# POWER_PMIC.net
KiCad netlist of a schematic drawn in Altium Designer
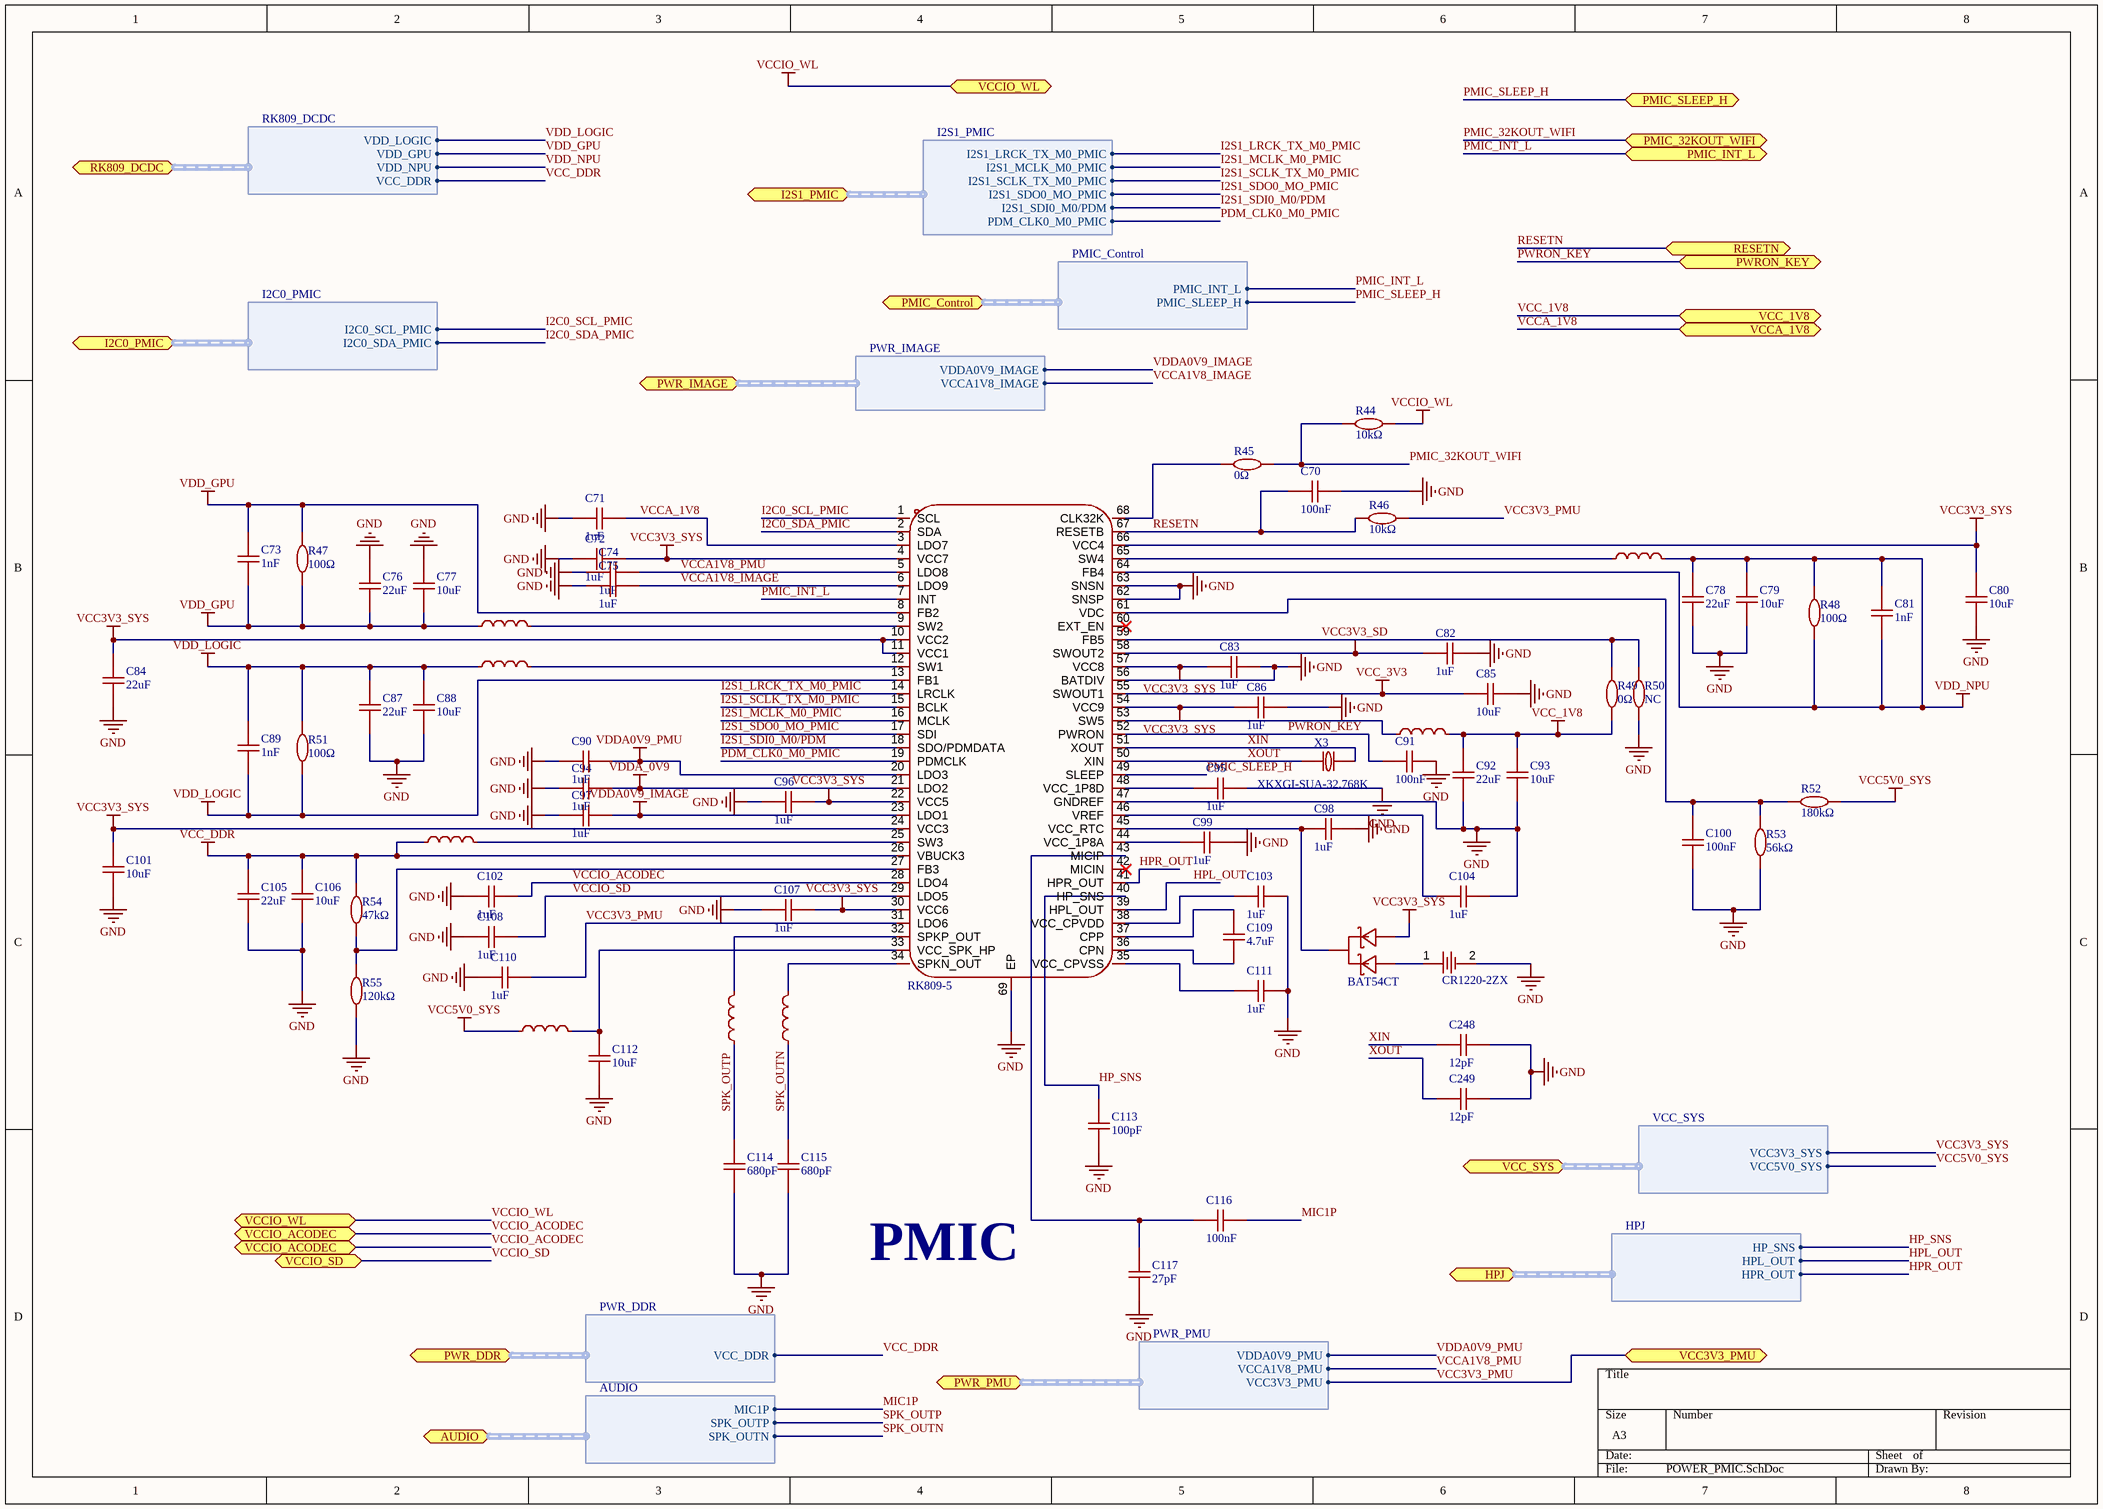
[diagram p0: POWER_PMIC.SchDoc]

(export (version "E")
  (design (tool "Eeschema 10.0.6"))
  (components
    (comp (ref "BT1")
      (value "CR1220-2ZX")
      (footprint "BAT-SMD_CR1220-2ZX")
      (description "Battery")
      (libsource (lib "Connector") (part "CR1220-2ZX"))
    )
    (comp (ref "C70")
      (value "100nF")
      (footprint "C0402")
      (description "50V 100nF X7R ±10% 0402 Ceramic Capacitors ROHS")
      (libsource (lib "RLC") (part "100nF"))
    )
    (comp (ref "C71")
      (value "1uF")
      (footprint "C0402")
      (description "50V 1uF X5R ±10% 0402 Ceramic Capacitors ROHS")
      (libsource (lib "RLC") (part "1uF"))
    )
    (comp (ref "C72")
      (value "1uF")
      (footprint "C0402")
      (description "50V 1uF X5R ±10% 0402 Ceramic Capacitors ROHS")
      (libsource (lib "RLC") (part "1uF"))
    )
    (comp (ref "C73")
      (value "1nF")
      (footprint "C0402")
      (description "50V 1nF X7R ±10% 0402 Ceramic Capacitors ROHS")
      (libsource (lib "RLC") (part "1nF"))
    )
    (comp (ref "C74")
      (value "1uF")
      (footprint "C0402")
      (description "50V 1uF X5R ±10% 0402 Ceramic Capacitors ROHS")
      (libsource (lib "RLC") (part "1uF"))
    )
    (comp (ref "C75")
      (value "1uF")
      (footprint "C0402")
      (description "50V 1uF X5R ±10% 0402 Ceramic Capacitors ROHS")
      (libsource (lib "RLC") (part "1uF"))
    )
    (comp (ref "C76")
      (value "22uF")
      (footprint "C0603")
      (description "16V 22uF X5R ±20% 0603 Ceramic Capacitors ROHS")
      (libsource (lib "RLC") (part "22uF"))
    )
    (comp (ref "C77")
      (value "10uF")
      (footprint "C0603")
      (description "10V 10uF X5R ±10% 0603 Ceramic Capacitors ROHS")
      (libsource (lib "RLC") (part "10uF"))
    )
    (comp (ref "C78")
      (value "22uF")
      (footprint "C0603")
      (description "16V 22uF X5R ±20% 0603 Ceramic Capacitors ROHS")
      (libsource (lib "RLC") (part "22uF"))
    )
    (comp (ref "C79")
      (value "10uF")
      (footprint "C0603")
      (description "10V 10uF X5R ±10% 0603 Ceramic Capacitors ROHS")
      (libsource (lib "RLC") (part "10uF"))
    )
    (comp (ref "C80")
      (value "10uF")
      (footprint "C0603")
      (description "10V 10uF X5R ±10% 0603 Ceramic Capacitors ROHS")
      (libsource (lib "RLC") (part "10uF"))
    )
    (comp (ref "C81")
      (value "1nF")
      (footprint "C0402")
      (description "50V 1nF X7R ±10% 0402 Ceramic Capacitors ROHS")
      (libsource (lib "RLC") (part "1nF"))
    )
    (comp (ref "C82")
      (value "1uF")
      (footprint "C0402")
      (description "50V 1uF X5R ±10% 0402 Ceramic Capacitors ROHS")
      (libsource (lib "RLC") (part "1uF"))
    )
    (comp (ref "C83")
      (value "1uF")
      (footprint "C0402")
      (description "50V 1uF X5R ±10% 0402 Ceramic Capacitors ROHS")
      (libsource (lib "RLC") (part "1uF"))
    )
    (comp (ref "C84")
      (value "22uF")
      (footprint "C0603")
      (description "16V 22uF X5R ±20% 0603 Ceramic Capacitors ROHS")
      (libsource (lib "RLC") (part "22uF"))
    )
    (comp (ref "C85")
      (value "10uF")
      (footprint "C0603")
      (description "10V 10uF X5R ±10% 0603 Ceramic Capacitors ROHS")
      (libsource (lib "RLC") (part "10uF"))
    )
    (comp (ref "C86")
      (value "1uF")
      (footprint "C0402")
      (description "50V 1uF X5R ±10% 0402 Ceramic Capacitors ROHS")
      (libsource (lib "RLC") (part "1uF"))
    )
    (comp (ref "C87")
      (value "22uF")
      (footprint "C0603")
      (description "16V 22uF X5R ±20% 0603 Ceramic Capacitors ROHS")
      (libsource (lib "RLC") (part "22uF"))
    )
    (comp (ref "C88")
      (value "10uF")
      (footprint "C0603")
      (description "10V 10uF X5R ±10% 0603 Ceramic Capacitors ROHS")
      (libsource (lib "RLC") (part "10uF"))
    )
    (comp (ref "C89")
      (value "1nF")
      (footprint "C0402")
      (description "50V 1nF X7R ±10% 0402 Ceramic Capacitors ROHS")
      (libsource (lib "RLC") (part "1nF"))
    )
    (comp (ref "C90")
      (value "1uF")
      (footprint "C0402")
      (description "50V 1uF X5R ±10% 0402 Ceramic Capacitors ROHS")
      (libsource (lib "RLC") (part "1uF"))
    )
    (comp (ref "C91")
      (value "100nF")
      (footprint "C0402")
      (description "50V 100nF X7R ±10% 0402 Ceramic Capacitors ROHS")
      (libsource (lib "RLC") (part "100nF"))
    )
    (comp (ref "C92")
      (value "22uF")
      (footprint "C0603")
      (description "16V 22uF X5R ±20% 0603 Ceramic Capacitors ROHS")
      (libsource (lib "RLC") (part "22uF"))
    )
    (comp (ref "C93")
      (value "10uF")
      (footprint "C0603")
      (description "10V 10uF X5R ±10% 0603 Ceramic Capacitors ROHS")
      (libsource (lib "RLC") (part "10uF"))
    )
    (comp (ref "C94")
      (value "1uF")
      (footprint "C0402")
      (description "50V 1uF X5R ±10% 0402 Ceramic Capacitors ROHS")
      (libsource (lib "RLC") (part "1uF"))
    )
    (comp (ref "C95")
      (value "1uF")
      (footprint "C0402")
      (description "50V 1uF X5R ±10% 0402 Ceramic Capacitors ROHS")
      (libsource (lib "RLC") (part "1uF"))
    )
    (comp (ref "C96")
      (value "1uF")
      (footprint "C0402")
      (description "50V 1uF X5R ±10% 0402 Ceramic Capacitors ROHS")
      (libsource (lib "RLC") (part "1uF"))
    )
    (comp (ref "C97")
      (value "1uF")
      (footprint "C0402")
      (description "50V 1uF X5R ±10% 0402 Ceramic Capacitors ROHS")
      (libsource (lib "RLC") (part "1uF"))
    )
    (comp (ref "C98")
      (value "1uF")
      (footprint "C0402")
      (description "50V 1uF X5R ±10% 0402 Ceramic Capacitors ROHS")
      (libsource (lib "RLC") (part "1uF"))
    )
    (comp (ref "C99")
      (value "1uF")
      (footprint "C0402")
      (description "50V 1uF X5R ±10% 0402 Ceramic Capacitors ROHS")
      (libsource (lib "RLC") (part "1uF"))
    )
    (comp (ref "C100")
      (value "100nF")
      (footprint "C0402")
      (description "50V 100nF X7R ±10% 0402 Ceramic Capacitors ROHS")
      (libsource (lib "RLC") (part "100nF"))
    )
    (comp (ref "C101")
      (value "10uF")
      (footprint "C0603")
      (description "10V 10uF X5R ±10% 0603 Ceramic Capacitors ROHS")
      (libsource (lib "RLC") (part "10uF"))
    )
    (comp (ref "C102")
      (value "1uF")
      (footprint "C0402")
      (description "50V 1uF X5R ±10% 0402 Ceramic Capacitors ROHS")
      (libsource (lib "RLC") (part "1uF"))
    )
    (comp (ref "C103")
      (value "1uF")
      (footprint "C0402")
      (description "50V 1uF X5R ±10% 0402 Ceramic Capacitors ROHS")
      (libsource (lib "RLC") (part "1uF"))
    )
    (comp (ref "C104")
      (value "1uF")
      (footprint "C0402")
      (description "50V 1uF X5R ±10% 0402 Ceramic Capacitors ROHS")
      (libsource (lib "RLC") (part "1uF"))
    )
    (comp (ref "C105")
      (value "22uF")
      (footprint "C0603")
      (description "16V 22uF X5R ±20% 0603 Ceramic Capacitors ROHS")
      (libsource (lib "RLC") (part "22uF"))
    )
    (comp (ref "C106")
      (value "10uF")
      (footprint "C0603")
      (description "10V 10uF X5R ±10% 0603 Ceramic Capacitors ROHS")
      (libsource (lib "RLC") (part "10uF"))
    )
    (comp (ref "C107")
      (value "1uF")
      (footprint "C0402")
      (description "50V 1uF X5R ±10% 0402 Ceramic Capacitors ROHS")
      (libsource (lib "RLC") (part "1uF"))
    )
    (comp (ref "C108")
      (value "1uF")
      (footprint "C0402")
      (description "50V 1uF X5R ±10% 0402 Ceramic Capacitors ROHS")
      (libsource (lib "RLC") (part "1uF"))
    )
    (comp (ref "C109")
      (value "4.7uF")
      (footprint "C0402")
      (description "10V 4.7uF X5R ±20% 0402 Ceramic Capacitors ROHS")
      (libsource (lib "RLC") (part "4.7uF"))
    )
    (comp (ref "C110")
      (value "1uF")
      (footprint "C0402")
      (description "50V 1uF X5R ±10% 0402 Ceramic Capacitors ROHS")
      (libsource (lib "RLC") (part "1uF"))
    )
    (comp (ref "C111")
      (value "1uF")
      (footprint "C0402")
      (description "50V 1uF X5R ±10% 0402 Ceramic Capacitors ROHS")
      (libsource (lib "RLC") (part "1uF"))
    )
    (comp (ref "C112")
      (value "10uF")
      (footprint "C0603")
      (description "10V 10uF X5R ±10% 0603 Ceramic Capacitors ROHS")
      (libsource (lib "RLC") (part "10uF"))
    )
    (comp (ref "C113")
      (value "100pF")
      (footprint "C0402")
      (description "50V 100pF C0G ±5% 0402 Ceramic Capacitors ROHS")
      (libsource (lib "RLC") (part "100pF"))
    )
    (comp (ref "C114")
      (value "680pF")
      (footprint "C0402")
      (description "50V 680pF C0G ±5% 0402 Ceramic Capacitors ROHS")
      (libsource (lib "RLC") (part "680pF"))
    )
    (comp (ref "C115")
      (value "680pF")
      (footprint "C0402")
      (description "50V 680pF C0G ±5% 0402 Ceramic Capacitors ROHS")
      (libsource (lib "RLC") (part "680pF"))
    )
    (comp (ref "C116")
      (value "100nF")
      (footprint "C0402")
      (description "50V 100nF X7R ±10% 0402 Ceramic Capacitors ROHS")
      (libsource (lib "RLC") (part "100nF"))
    )
    (comp (ref "C117")
      (value "27pF")
      (footprint "C0402")
      (description "50V 27pF C0G ±5% 0402 Ceramic Capacitors ROHS")
      (libsource (lib "RLC") (part "27pF"))
    )
    (comp (ref "C248")
      (value "12pF")
      (footprint "C0402")
      (description "50V 12pF C0G ±5% 0402 Ceramic Capacitors ROHS")
      (libsource (lib "RLC") (part "12pF"))
    )
    (comp (ref "C249")
      (value "12pF")
      (footprint "C0402")
      (description "50V 12pF C0G ±5% 0402 Ceramic Capacitors ROHS")
      (libsource (lib "RLC") (part "12pF"))
    )
    (comp (ref "D9")
      (value "BAT54CT")
      (footprint "SOT-523-3_L1.6-W0.8-P1.00-LS1.6-BR")
      (description "电压:30V 电流:200mA 特性：低正向压降。 快速开关。 PN结保护环，用于瞬态和ESD保护")
      (libsource (lib "LED") (part "BAT54CT"))
    )
    (comp (ref "L3")
      (value "470nH")
      (footprint "IND-SMD_L2.0-W1.6_MHCHL201610A-1R0M-Q8A")
      (description "0806 MCS20FC-R47MHC")
      (fields
        (field (name "MANUFACTURER") "Sunltech(顺磁)")
        (field (name "MANUFACTURER PART") "SLW4030S1R0NST")
      )
      (libsource (lib "RLC") (part "MCS20FC-R47MHC"))
    )
    (comp (ref "L4")
      (value "470nH")
      (footprint "IND-SMD_L2.0-W1.6_MHCHL201610A-1R0M-Q8A")
      (description "0806 MCS20FC-R47MHC")
      (fields
        (field (name "MANUFACTURER") "Sunltech(顺磁)")
        (field (name "MANUFACTURER PART") "SLW4030S1R0NST")
      )
      (libsource (lib "RLC") (part "MCS20FC-R47MHC"))
    )
    (comp (ref "L5")
      (value "470nH")
      (footprint "IND-SMD_L2.0-W1.6_MHCHL201610A-1R0M-Q8A")
      (description "0806 MCS20FC-R47MHC")
      (fields
        (field (name "MANUFACTURER") "Sunltech(顺磁)")
        (field (name "MANUFACTURER PART") "SLW4030S1R0NST")
      )
      (libsource (lib "RLC") (part "MCS20FC-R47MHC"))
    )
    (comp (ref "L6")
      (value "470nH")
      (footprint "IND-SMD_L2.0-W1.6_MHCHL201610A-1R0M-Q8A")
      (description "0806 MCS20FC-R47MHC")
      (fields
        (field (name "MANUFACTURER") "Sunltech(顺磁)")
        (field (name "MANUFACTURER PART") "SLW4030S1R0NST")
      )
      (libsource (lib "RLC") (part "MCS20FC-R47MHC"))
    )
    (comp (ref "L7")
      (value "470nH")
      (footprint "IND-SMD_L2.0-W1.6_MHCHL201610A-1R0M-Q8A")
      (description "0806 MCS20FC-R47MHC")
      (fields
        (field (name "MANUFACTURER") "Sunltech(顺磁)")
        (field (name "MANUFACTURER PART") "SLW4030S1R0NST")
      )
      (libsource (lib "RLC") (part "MCS20FC-R47MHC"))
    )
    (comp (ref "L8")
      (value "180Ω")
      (footprint "L0603")
      (description "单路 0603磁珠 阻抗180Ω@100MHz")
      (fields (field (name "MANUFACTURER") "cjiang(长江微电)") (field (name "MANUFACTURER PART") "FNR6020S4R7MT"))
      (libsource (lib "RLC") (part "BLM18PG181SN1D"))
    )
    (comp (ref "L9")
      (value "180Ω")
      (footprint "L0603")
      (description "单路 0603磁珠 阻抗180Ω@100MHz")
      (fields (field (name "MANUFACTURER") "cjiang(长江微电)") (field (name "MANUFACTURER PART") "FNR6020S4R7MT"))
      (libsource (lib "RLC") (part "BLM18PG181SN1D"))
    )
    (comp (ref "L10")
      (value "180Ω")
      (footprint "L0603")
      (description "单路 0603磁珠 阻抗180Ω@100MHz")
      (fields (field (name "MANUFACTURER") "cjiang(长江微电)") (field (name "MANUFACTURER PART") "FNR6020S4R7MT"))
      (libsource (lib "RLC") (part "BLM18PG181SN1D"))
    )
    (comp (ref "R44")
      (value "10kΩ")
      (footprint "R0402")
      (description "62.5mW 10kΩ 50V ±100ppm/℃ Thick Film Resistor ±1% 0402 Chip Resistor - Surface Mount ROHS")
      (libsource (lib "RLC") (part "10kΩ"))
    )
    (comp (ref "R45")
      (value "0Ω")
      (footprint "R0402")
      (description "0Ω 62.5mW 50V Thick Film Resistor ±1% 0402 Chip Resistor - Surface Mount ROHS")
      (libsource (lib "RLC") (part "0Ω"))
    )
    (comp (ref "R46")
      (value "10kΩ")
      (footprint "R0402")
      (description "62.5mW 10kΩ 50V ±100ppm/℃ Thick Film Resistor ±1% 0402 Chip Resistor - Surface Mount ROHS")
      (libsource (lib "RLC") (part "10kΩ"))
    )
    (comp (ref "R47")
      (value "100Ω")
      (footprint "R0402")
      (description "100Ω 62.5mW 50V ±100ppm/℃ Thick Film Resistor ±1% 0402 Chip Resistor - Surface Mount ROHS")
      (libsource (lib "RLC") (part "100Ω"))
    )
    (comp (ref "R48")
      (value "100Ω")
      (footprint "R0402")
      (description "100Ω 62.5mW 50V ±100ppm/℃ Thick Film Resistor ±1% 0402 Chip Resistor - Surface Mount ROHS")
      (libsource (lib "RLC") (part "100Ω"))
    )
    (comp (ref "R49")
      (value "0Ω")
      (footprint "R0402")
      (description "0Ω 62.5mW 50V Thick Film Resistor ±1% 0402 Chip Resistor - Surface Mount ROHS")
      (libsource (lib "RLC") (part "0Ω"))
    )
    (comp (ref "R50")
      (value "NC")
      (footprint "R0402")
      (description "0Ω 62.5mW 50V Thick Film Resistor ±1% 0402 Chip Resistor - Surface Mount ROHS")
      (libsource (lib "RLC") (part "0Ω"))
    )
    (comp (ref "R51")
      (value "100Ω")
      (footprint "R0402")
      (description "100Ω 62.5mW 50V ±100ppm/℃ Thick Film Resistor ±1% 0402 Chip Resistor - Surface Mount ROHS")
      (libsource (lib "RLC") (part "100Ω"))
    )
    (comp (ref "R52")
      (value "180kΩ")
      (footprint "R0402")
      (description "62.5mW 180kΩ 50V ±100ppm/℃ Thick Film Resistor ±1% 0402 Chip Resistor - Surface Mount ROHS")
      (libsource (lib "RLC") (part "180kΩ"))
    )
    (comp (ref "R53")
      (value "56kΩ")
      (footprint "R0402")
      (description "56kΩ 62.5mW 50V ±100ppm/℃ Thick Film Resistor ±1% 0402 Chip Resistor - Surface Mount ROHS")
      (libsource (lib "RLC") (part "56kΩ"))
    )
    (comp (ref "R54")
      (value "47kΩ")
      (footprint "R0402")
      (description "62.5mW 47kΩ 50V ±100ppm/℃ Thick Film Resistor ±1% 0402 Chip Resistor - Surface Mount ROHS")
      (libsource (lib "RLC") (part "47kΩ"))
    )
    (comp (ref "R55")
      (value "120kΩ")
      (footprint "R0402")
      (description "62.5mW 120kΩ 50V ±100ppm/℃ Thick Film Resistor ±1% 0402 Chip Resistor - Surface Mount ROHS")
      (libsource (lib "RLC") (part "120kΩ"))
    )
    (comp (ref "U20")
      (value "RK809-5")
      (footprint "QFN-68_L7.0-W7.0-P0.35-BL-EP5.5")
      (libsource (lib "IC") (part "RK809-5"))
    )
    (comp (ref "X3")
      (value "XKXGI-SUA-32.768K")
      (footprint "CRYSTAL-SMD_L3.2-W1.5-1")
      (description "SMD3215-2P XKXGI-SUA-32.768K")
      (libsource (lib "OSC") (part "XKXGI-SUA-32.768K"))
    )
  )
  (nets
    (net (code "11") (name "/HPL_OUT") (class "Default")
      (node (ref "U20") (pin "39") (pinfunction "HPL_OUT_39") (pintype "passive"))
    )
    (net (code "12") (name "/HPR_OUT") (class "Default")
      (node (ref "U20") (pin "41") (pinfunction "HPR_OUT_41") (pintype "passive"))
    )
    (net (code "13") (name "/HP_SNS") (class "Default")
      (node (ref "C113") (pin "2") (pinfunction "2_2") (pintype "passive"))
      (node (ref "U20") (pin "40") (pinfunction "HP_SNS_40") (pintype "passive"))
    )
    (net (code "14") (name "/I2C0_SCL_PMIC") (class "Default")
      (node (ref "U20") (pin "1") (pinfunction "SCL_1") (pintype "passive"))
    )
    (net (code "15") (name "/I2C0_SDA_PMIC") (class "Default")
      (node (ref "U20") (pin "2") (pinfunction "SDA_2") (pintype "passive"))
    )
    (net (code "16") (name "/I2S1_LRCK_TX_M0_PMIC") (class "Default")
      (node (ref "U20") (pin "14") (pinfunction "LRCLK_14") (pintype "passive"))
    )
    (net (code "17") (name "/I2S1_MCLK_M0_PMIC") (class "Default")
      (node (ref "U20") (pin "16") (pinfunction "MCLK_16") (pintype "passive"))
    )
    (net (code "18") (name "/I2S1_SCLK_TX_M0_PMIC") (class "Default")
      (node (ref "U20") (pin "15") (pinfunction "BCLK_15") (pintype "passive"))
    )
    (net (code "19") (name "/I2S1_SDI0_M0{slash}PDM") (class "Default")
      (node (ref "U20") (pin "18") (pinfunction "SDO/PDMDATA_18") (pintype "passive"))
    )
    (net (code "20") (name "/I2S1_SDO0_MO_PMIC") (class "Default")
      (node (ref "U20") (pin "17") (pinfunction "SDI_17") (pintype "passive"))
    )
    (net (code "21") (name "/MIC1P") (class "Default")
      (node (ref "C116") (pin "2") (pinfunction "2_2") (pintype "passive"))
    )
    (net (code "22") (name "/PDM_CLK0_M0_PMIC") (class "Default")
      (node (ref "U20") (pin "19") (pinfunction "PDMCLK_19") (pintype "passive"))
    )
    (net (code "23") (name "/PMIC_32KOUT_WIFI") (class "Default")
      (node (ref "R44") (pin "1") (pinfunction "1_1") (pintype "passive"))
      (node (ref "R45") (pin "2") (pinfunction "2_2") (pintype "passive"))
    )
    (net (code "24") (name "/PMIC_INT_L") (class "Default")
      (node (ref "U20") (pin "7") (pinfunction "INT_7") (pintype "passive"))
    )
    (net (code "25") (name "/PMIC_SLEEP_H") (class "Default")
      (node (ref "U20") (pin "49") (pinfunction "SLEEP_49") (pintype "passive"))
    )
    (net (code "26") (name "/PWRON_KEY") (class "Default")
      (node (ref "C91") (pin "1") (pinfunction "1_1") (pintype "passive"))
      (node (ref "U20") (pin "52") (pinfunction "PWRON_52") (pintype "passive"))
    )
    (net (code "27") (name "/RESETN") (class "Default")
      (node (ref "C70") (pin "1") (pinfunction "1_1") (pintype "passive"))
      (node (ref "R46") (pin "1") (pinfunction "1_1") (pintype "passive"))
      (node (ref "U20") (pin "67") (pinfunction "RESETB_67") (pintype "passive"))
    )
    (net (code "28") (name "/SPK_OUTN") (class "Default")
      (node (ref "C115") (pin "2") (pinfunction "2_2") (pintype "passive"))
      (node (ref "L9") (pin "1") (pinfunction "1_1") (pintype "passive"))
    )
    (net (code "29") (name "/SPK_OUTP") (class "Default")
      (node (ref "C114") (pin "2") (pinfunction "2_2") (pintype "passive"))
      (node (ref "L8") (pin "1") (pinfunction "1_1") (pintype "passive"))
    )
    (net (code "30") (name "/VCC3V3_PMU") (class "Default")
      (node (ref "C110") (pin "1") (pinfunction "1_1") (pintype "passive"))
      (node (ref "R46") (pin "2") (pinfunction "2_2") (pintype "passive"))
      (node (ref "U20") (pin "31") (pinfunction "LDO6_31") (pintype "passive"))
    )
    (net (code "31") (name "/VCCA1V8_IMAGE") (class "Default")
      (node (ref "C75") (pin "1") (pinfunction "1_1") (pintype "passive"))
      (node (ref "U20") (pin "6") (pinfunction "LDO9_6") (pintype "passive"))
    )
    (net (code "32") (name "/VCCA1V8_PMU") (class "Default")
      (node (ref "C74") (pin "1") (pinfunction "1_1") (pintype "passive"))
      (node (ref "U20") (pin "5") (pinfunction "LDO8_5") (pintype "passive"))
    )
    (net (code "33") (name "/VCCA_1V8") (class "Default")
      (node (ref "C71") (pin "1") (pinfunction "1_1") (pintype "passive"))
      (node (ref "U20") (pin "3") (pinfunction "LDO7_3") (pintype "passive"))
    )
    (net (code "34") (name "/VCCIO_ACODEC") (class "Default")
      (node (ref "C102") (pin "1") (pinfunction "1_1") (pintype "passive"))
      (node (ref "U20") (pin "28") (pinfunction "LDO4_28") (pintype "passive"))
    )
    (net (code "35") (name "/VCCIO_SD") (class "Default")
      (node (ref "C108") (pin "1") (pinfunction "1_1") (pintype "passive"))
      (node (ref "U20") (pin "29") (pinfunction "LDO5_29") (pintype "passive"))
    )
    (net (code "36") (name "/XIN") (class "Default")
      (node (ref "C248") (pin "1") (pinfunction "1_1") (pintype "passive"))
      (node (ref "U20") (pin "51") (pinfunction "XOUT_51") (pintype "passive"))
      (node (ref "X3") (pin "2") (pinfunction "2_2") (pintype "passive"))
    )
    (net (code "37") (name "/XOUT") (class "Default")
      (node (ref "C249") (pin "1") (pinfunction "1_1") (pintype "passive"))
      (node (ref "U20") (pin "50") (pinfunction "XIN_50") (pintype "passive"))
      (node (ref "X3") (pin "1") (pinfunction "1_1") (pintype "passive"))
    )
    (net (code "48") (name "GND") (class "Default")
      (node (ref "BT1") (pin "2") (pinfunction "2_2") (pintype "passive"))
      (node (ref "C100") (pin "1") (pinfunction "1_1") (pintype "passive"))
      (node (ref "C101") (pin "1") (pinfunction "1_1") (pintype "passive"))
      (node (ref "C102") (pin "2") (pinfunction "2_2") (pintype "passive"))
      (node (ref "C103") (pin "1") (pinfunction "1_1") (pintype "passive"))
      (node (ref "C104") (pin "1") (pinfunction "1_1") (pintype "passive"))
      (node (ref "C105") (pin "1") (pinfunction "1_1") (pintype "passive"))
      (node (ref "C106") (pin "1") (pinfunction "1_1") (pintype "passive"))
      (node (ref "C107") (pin "2") (pinfunction "2_2") (pintype "passive"))
      (node (ref "C108") (pin "2") (pinfunction "2_2") (pintype "passive"))
      (node (ref "C110") (pin "2") (pinfunction "2_2") (pintype "passive"))
      (node (ref "C111") (pin "2") (pinfunction "2_2") (pintype "passive"))
      (node (ref "C112") (pin "1") (pinfunction "1_1") (pintype "passive"))
      (node (ref "C113") (pin "1") (pinfunction "1_1") (pintype "passive"))
      (node (ref "C114") (pin "1") (pinfunction "1_1") (pintype "passive"))
      (node (ref "C115") (pin "1") (pinfunction "1_1") (pintype "passive"))
      (node (ref "C117") (pin "1") (pinfunction "1_1") (pintype "passive"))
      (node (ref "C248") (pin "2") (pinfunction "2_2") (pintype "passive"))
      (node (ref "C249") (pin "2") (pinfunction "2_2") (pintype "passive"))
      (node (ref "C70") (pin "2") (pinfunction "2_2") (pintype "passive"))
      (node (ref "C71") (pin "2") (pinfunction "2_2") (pintype "passive"))
      (node (ref "C72") (pin "2") (pinfunction "2_2") (pintype "passive"))
      (node (ref "C74") (pin "2") (pinfunction "2_2") (pintype "passive"))
      (node (ref "C75") (pin "2") (pinfunction "2_2") (pintype "passive"))
      (node (ref "C76") (pin "2") (pinfunction "2_2") (pintype "passive"))
      (node (ref "C77") (pin "2") (pinfunction "2_2") (pintype "passive"))
      (node (ref "C78") (pin "1") (pinfunction "1_1") (pintype "passive"))
      (node (ref "C79") (pin "1") (pinfunction "1_1") (pintype "passive"))
      (node (ref "C80") (pin "1") (pinfunction "1_1") (pintype "passive"))
      (node (ref "C82") (pin "1") (pinfunction "1_1") (pintype "passive"))
      (node (ref "C83") (pin "2") (pinfunction "2_2") (pintype "passive"))
      (node (ref "C84") (pin "1") (pinfunction "1_1") (pintype "passive"))
      (node (ref "C85") (pin "1") (pinfunction "1_1") (pintype "passive"))
      (node (ref "C86") (pin "2") (pinfunction "2_2") (pintype "passive"))
      (node (ref "C87") (pin "1") (pinfunction "1_1") (pintype "passive"))
      (node (ref "C88") (pin "1") (pinfunction "1_1") (pintype "passive"))
      (node (ref "C90") (pin "2") (pinfunction "2_2") (pintype "passive"))
      (node (ref "C91") (pin "2") (pinfunction "2_2") (pintype "passive"))
      (node (ref "C92") (pin "1") (pinfunction "1_1") (pintype "passive"))
      (node (ref "C93") (pin "1") (pinfunction "1_1") (pintype "passive"))
      (node (ref "C94") (pin "2") (pinfunction "2_2") (pintype "passive"))
      (node (ref "C95") (pin "2") (pinfunction "2_2") (pintype "passive"))
      (node (ref "C96") (pin "2") (pinfunction "2_2") (pintype "passive"))
      (node (ref "C97") (pin "2") (pinfunction "2_2") (pintype "passive"))
      (node (ref "C98") (pin "1") (pinfunction "1_1") (pintype "passive"))
      (node (ref "C99") (pin "2") (pinfunction "2_2") (pintype "passive"))
      (node (ref "R50") (pin "2") (pinfunction "2_2") (pintype "passive"))
      (node (ref "R53") (pin "1") (pinfunction "1_1") (pintype "passive"))
      (node (ref "R55") (pin "1") (pinfunction "1_1") (pintype "passive"))
      (node (ref "U20") (pin "47") (pinfunction "GNDREF_47") (pintype "passive"))
      (node (ref "U20") (pin "56") (pinfunction "BATDIV_56") (pintype "passive"))
      (node (ref "U20") (pin "62") (pinfunction "SNSP_62") (pintype "passive"))
      (node (ref "U20") (pin "63") (pinfunction "SNSN_63") (pintype "passive"))
      (node (ref "U20") (pin "69") (pinfunction "EP_69") (pintype "passive"))
    )
    (net (code "49") (name "Net-(BT1-Pad1)") (class "Default")
      (node (ref "BT1") (pin "1") (pinfunction "1_1") (pintype "passive"))
      (node (ref "D9") (pin "1") (pinfunction "A_1") (pintype "passive"))
    )
    (net (code "50") (name "Net-(D9-K)") (class "Default")
      (node (ref "C98") (pin "2") (pinfunction "2_2") (pintype "passive"))
      (node (ref "D9") (pin "3") (pinfunction "K_3") (pintype "passive"))
      (node (ref "U20") (pin "45") (pinfunction "VCC_RTC_45") (pintype "passive"))
    )
    (net (code "51") (name "Net-(U20-CLK32K)") (class "Default")
      (node (ref "R45") (pin "1") (pinfunction "1_1") (pintype "passive"))
      (node (ref "U20") (pin "68") (pinfunction "CLK32K_68") (pintype "passive"))
    )
    (net (code "52") (name "Net-(U20-CPN)") (class "Default")
      (node (ref "C109") (pin "1") (pinfunction "1_1") (pintype "passive"))
      (node (ref "U20") (pin "36") (pinfunction "CPN_36") (pintype "passive"))
    )
    (net (code "53") (name "Net-(U20-CPP)") (class "Default")
      (node (ref "C109") (pin "2") (pinfunction "2_2") (pintype "passive"))
      (node (ref "U20") (pin "37") (pinfunction "CPP_37") (pintype "passive"))
    )
    (net (code "54") (name "Net-(U20-FB3)") (class "Default")
      (node (ref "R54") (pin "1") (pinfunction "1_1") (pintype "passive"))
      (node (ref "R55") (pin "2") (pinfunction "2_2") (pintype "passive"))
      (node (ref "U20") (pin "27") (pinfunction "FB3_27") (pintype "passive"))
    )
    (net (code "55") (name "Net-(U20-FB5)") (class "Default")
      (node (ref "R49") (pin "2") (pinfunction "2_2") (pintype "passive"))
      (node (ref "R50") (pin "1") (pinfunction "1_1") (pintype "passive"))
      (node (ref "U20") (pin "59") (pinfunction "FB5_59") (pintype "passive"))
    )
    (net (code "56") (name "Net-(U20-MICIP)") (class "Default")
      (node (ref "C116") (pin "1") (pinfunction "1_1") (pintype "passive"))
      (node (ref "C117") (pin "2") (pinfunction "2_2") (pintype "passive"))
      (node (ref "U20") (pin "43") (pinfunction "MICIP_43") (pintype "passive"))
    )
    (net (code "57") (name "Net-(U20-SPKN_OUT)") (class "Default")
      (node (ref "L9") (pin "2") (pinfunction "2_2") (pintype "passive"))
      (node (ref "U20") (pin "34") (pinfunction "SPKN_OUT_34") (pintype "passive"))
    )
    (net (code "58") (name "Net-(U20-SPKP_OUT)") (class "Default")
      (node (ref "L8") (pin "2") (pinfunction "2_2") (pintype "passive"))
      (node (ref "U20") (pin "32") (pinfunction "SPKP_OUT_32") (pintype "passive"))
    )
    (net (code "59") (name "Net-(U20-SW1)") (class "Default")
      (node (ref "L5") (pin "2") (pinfunction "2_2") (pintype "passive"))
      (node (ref "U20") (pin "12") (pinfunction "SW1_12") (pintype "passive"))
    )
    (net (code "60") (name "Net-(U20-SW2)") (class "Default")
      (node (ref "L4") (pin "2") (pinfunction "2_2") (pintype "passive"))
      (node (ref "U20") (pin "9") (pinfunction "SW2_9") (pintype "passive"))
    )
    (net (code "61") (name "Net-(U20-SW3)") (class "Default")
      (node (ref "L7") (pin "2") (pinfunction "2_2") (pintype "passive"))
      (node (ref "U20") (pin "25") (pinfunction "SW3_25") (pintype "passive"))
    )
    (net (code "62") (name "Net-(U20-SW4)") (class "Default")
      (node (ref "L3") (pin "1") (pinfunction "1_1") (pintype "passive"))
      (node (ref "U20") (pin "65") (pinfunction "SW4_65") (pintype "passive"))
    )
    (net (code "63") (name "Net-(U20-SW5)") (class "Default")
      (node (ref "L6") (pin "1") (pinfunction "1_1") (pintype "passive"))
      (node (ref "U20") (pin "53") (pinfunction "SW5_53") (pintype "passive"))
    )
    (net (code "64") (name "Net-(U20-VCC_1P8A)") (class "Default")
      (node (ref "C99") (pin "1") (pinfunction "1_1") (pintype "passive"))
      (node (ref "U20") (pin "44") (pinfunction "VCC_1P8A_44") (pintype "passive"))
    )
    (net (code "65") (name "Net-(U20-VCC_1P8D)") (class "Default")
      (node (ref "C95") (pin "1") (pinfunction "1_1") (pintype "passive"))
      (node (ref "U20") (pin "48") (pinfunction "VCC_1P8D_48") (pintype "passive"))
    )
    (net (code "66") (name "Net-(U20-VCC_CPVDD)") (class "Default")
      (node (ref "C103") (pin "2") (pinfunction "2_2") (pintype "passive"))
      (node (ref "U20") (pin "38") (pinfunction "VCC_CPVDD_38") (pintype "passive"))
    )
    (net (code "67") (name "Net-(U20-VCC_CPVSS)") (class "Default")
      (node (ref "C111") (pin "1") (pinfunction "1_1") (pintype "passive"))
      (node (ref "U20") (pin "35") (pinfunction "VCC_CPVSS_35") (pintype "passive"))
    )
    (net (code "68") (name "Net-(U20-VCC_SPK_HP)") (class "Default")
      (node (ref "C112") (pin "2") (pinfunction "2_2") (pintype "passive"))
      (node (ref "L10") (pin "2") (pinfunction "2_2") (pintype "passive"))
      (node (ref "U20") (pin "33") (pinfunction "VCC_SPK_HP_33") (pintype "passive"))
    )
    (net (code "69") (name "Net-(U20-VDC)") (class "Default")
      (node (ref "C100") (pin "2") (pinfunction "2_2") (pintype "passive"))
      (node (ref "R52") (pin "1") (pinfunction "1_1") (pintype "passive"))
      (node (ref "R53") (pin "2") (pinfunction "2_2") (pintype "passive"))
      (node (ref "U20") (pin "61") (pinfunction "VDC_61") (pintype "passive"))
    )
    (net (code "70") (name "Net-(U20-VREF)") (class "Default")
      (node (ref "C104") (pin "2") (pinfunction "2_2") (pintype "passive"))
      (node (ref "U20") (pin "46") (pinfunction "VREF_46") (pintype "passive"))
    )
    (net (code "71") (name "VCC3V3_SD") (class "Default")
      (node (ref "C82") (pin "2") (pinfunction "2_2") (pintype "passive"))
      (node (ref "U20") (pin "58") (pinfunction "SWOUT2_58") (pintype "passive"))
    )
    (net (code "72") (name "VCC3V3_SYS") (class "Default")
      (node (ref "C101") (pin "2") (pinfunction "2_2") (pintype "passive"))
      (node (ref "C107") (pin "1") (pinfunction "1_1") (pintype "passive"))
      (node (ref "C72") (pin "1") (pinfunction "1_1") (pintype "passive"))
      (node (ref "C80") (pin "2") (pinfunction "2_2") (pintype "passive"))
      (node (ref "C83") (pin "1") (pinfunction "1_1") (pintype "passive"))
      (node (ref "C84") (pin "2") (pinfunction "2_2") (pintype "passive"))
      (node (ref "C86") (pin "1") (pinfunction "1_1") (pintype "passive"))
      (node (ref "C96") (pin "1") (pinfunction "1_1") (pintype "passive"))
      (node (ref "D9") (pin "2") (pinfunction "A_2") (pintype "passive"))
      (node (ref "U20") (pin "10") (pinfunction "VCC2_10") (pintype "passive"))
      (node (ref "U20") (pin "11") (pinfunction "VCC1_11") (pintype "passive"))
      (node (ref "U20") (pin "22") (pinfunction "VCC5_22") (pintype "passive"))
      (node (ref "U20") (pin "24") (pinfunction "VCC3_24") (pintype "passive"))
      (node (ref "U20") (pin "30") (pinfunction "VCC6_30") (pintype "passive"))
      (node (ref "U20") (pin "4") (pinfunction "VCC7_4") (pintype "passive"))
      (node (ref "U20") (pin "54") (pinfunction "VCC9_54") (pintype "passive"))
      (node (ref "U20") (pin "57") (pinfunction "VCC8_57") (pintype "passive"))
      (node (ref "U20") (pin "66") (pinfunction "VCC4_66") (pintype "passive"))
    )
    (net (code "73") (name "VCC5V0_SYS") (class "Default")
      (node (ref "L10") (pin "1") (pinfunction "1_1") (pintype "passive"))
      (node (ref "R52") (pin "2") (pinfunction "2_2") (pintype "passive"))
    )
    (net (code "74") (name "VCCIO_WL") (class "Default")
      (node (ref "R44") (pin "2") (pinfunction "2_2") (pintype "passive"))
    )
    (net (code "75") (name "VCC_1V8") (class "Default")
      (node (ref "C92") (pin "2") (pinfunction "2_2") (pintype "passive"))
      (node (ref "C93") (pin "2") (pinfunction "2_2") (pintype "passive"))
      (node (ref "L6") (pin "2") (pinfunction "2_2") (pintype "passive"))
      (node (ref "R49") (pin "1") (pinfunction "1_1") (pintype "passive"))
    )
    (net (code "76") (name "VCC_3V3") (class "Default")
      (node (ref "C85") (pin "2") (pinfunction "2_2") (pintype "passive"))
      (node (ref "U20") (pin "55") (pinfunction "SWOUT1_55") (pintype "passive"))
    )
    (net (code "77") (name "VCC_DDR") (class "Default")
      (node (ref "C105") (pin "2") (pinfunction "2_2") (pintype "passive"))
      (node (ref "C106") (pin "2") (pinfunction "2_2") (pintype "passive"))
      (node (ref "L7") (pin "1") (pinfunction "1_1") (pintype "passive"))
      (node (ref "R54") (pin "2") (pinfunction "2_2") (pintype "passive"))
      (node (ref "U20") (pin "26") (pinfunction "VBUCK3_26") (pintype "passive"))
    )
    (net (code "78") (name "VDDA0V9_IMAGE") (class "Default")
      (node (ref "C97") (pin "1") (pinfunction "1_1") (pintype "passive"))
      (node (ref "U20") (pin "23") (pinfunction "LDO1_23") (pintype "passive"))
    )
    (net (code "79") (name "VDDA0V9_PMU") (class "Default")
      (node (ref "C90") (pin "1") (pinfunction "1_1") (pintype "passive"))
      (node (ref "U20") (pin "20") (pinfunction "LDO3_20") (pintype "passive"))
    )
    (net (code "80") (name "VDDA_0V9") (class "Default")
      (node (ref "C94") (pin "1") (pinfunction "1_1") (pintype "passive"))
      (node (ref "U20") (pin "21") (pinfunction "LDO2_21") (pintype "passive"))
    )
    (net (code "81") (name "VDD_GPU") (class "Default")
      (node (ref "C73") (pin "1") (pinfunction "1_1") (pintype "passive"))
      (node (ref "C73") (pin "2") (pinfunction "2_2") (pintype "passive"))
      (node (ref "C76") (pin "1") (pinfunction "1_1") (pintype "passive"))
      (node (ref "C77") (pin "1") (pinfunction "1_1") (pintype "passive"))
      (node (ref "L4") (pin "1") (pinfunction "1_1") (pintype "passive"))
      (node (ref "R47") (pin "1") (pinfunction "1_1") (pintype "passive"))
      (node (ref "R47") (pin "2") (pinfunction "2_2") (pintype "passive"))
      (node (ref "U20") (pin "8") (pinfunction "FB2_8") (pintype "passive"))
    )
    (net (code "82") (name "VDD_LOGIC") (class "Default")
      (node (ref "C87") (pin "2") (pinfunction "2_2") (pintype "passive"))
      (node (ref "C88") (pin "2") (pinfunction "2_2") (pintype "passive"))
      (node (ref "C89") (pin "1") (pinfunction "1_1") (pintype "passive"))
      (node (ref "C89") (pin "2") (pinfunction "2_2") (pintype "passive"))
      (node (ref "L5") (pin "1") (pinfunction "1_1") (pintype "passive"))
      (node (ref "R51") (pin "1") (pinfunction "1_1") (pintype "passive"))
      (node (ref "R51") (pin "2") (pinfunction "2_2") (pintype "passive"))
      (node (ref "U20") (pin "13") (pinfunction "FB1_13") (pintype "passive"))
    )
    (net (code "83") (name "VDD_NPU") (class "Default")
      (node (ref "C78") (pin "2") (pinfunction "2_2") (pintype "passive"))
      (node (ref "C79") (pin "2") (pinfunction "2_2") (pintype "passive"))
      (node (ref "C81") (pin "1") (pinfunction "1_1") (pintype "passive"))
      (node (ref "C81") (pin "2") (pinfunction "2_2") (pintype "passive"))
      (node (ref "L3") (pin "2") (pinfunction "2_2") (pintype "passive"))
      (node (ref "R48") (pin "1") (pinfunction "1_1") (pintype "passive"))
      (node (ref "R48") (pin "2") (pinfunction "2_2") (pintype "passive"))
      (node (ref "U20") (pin "64") (pinfunction "FB4_64") (pintype "passive"))
    )
    (net (code "84") (name "unconnected-(U20-EXT_EN-Pad60)") (class "Default")
      (node (ref "U20") (pin "60") (pinfunction "EXT_EN_60") (pintype "passive+no_connect"))
    )
    (net (code "85") (name "unconnected-(U20-MICIN-Pad42)") (class "Default")
      (node (ref "U20") (pin "42") (pinfunction "MICIN_42") (pintype "passive+no_connect"))
    )
  )
)
